# Thermometers.net
KiCad netlist of a schematic drawn in Altium Designer
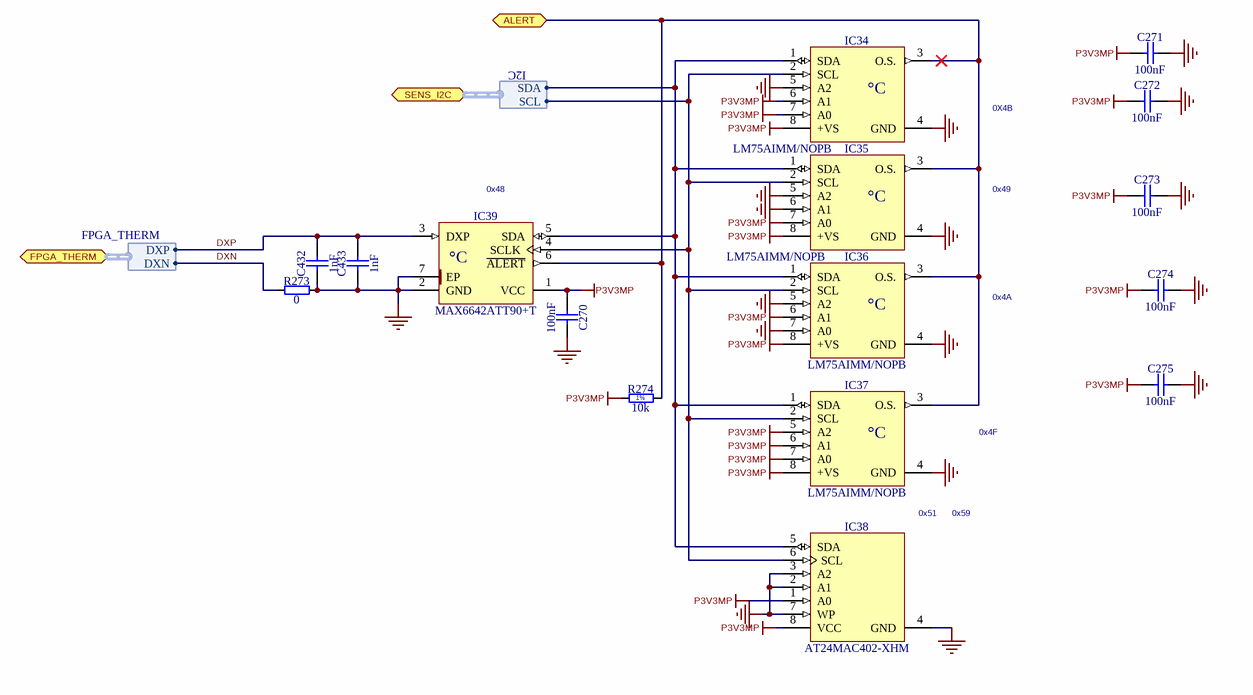
[diagram p0: Thermometers.SchDoc]

(export (version "E")
  (design (tool "Eeschema 10.0.6"))
  (components
    (comp (ref "C270")
      (value "100nF")
      (footprint "CAPC0603X33N")
      (description "Non-polarised capacitor")
      (fields
        (field (name "MANUFACTURER PART NUMBER") "CC0201_100NF_6.3V_10%_X5R")
        (field (name "MANUFACTURER") "GENERIC")
        (field (name "AUTHOR") "CERN DEM JLC")
      )
      (libsource (lib "Capacitors") (part "Capacitor - non polarized"))
    )
    (comp (ref "C271")
      (value "100nF")
      (footprint "CAPC0603X33N")
      (description "Non-polarised capacitor")
      (fields
        (field (name "MANUFACTURER PART NUMBER") "CC0201_100NF_6.3V_10%_X5R")
        (field (name "MANUFACTURER") "GENERIC")
        (field (name "AUTHOR") "CERN DEM JLC")
      )
      (libsource (lib "Capacitors") (part "Capacitor - non polarized"))
    )
    (comp (ref "C272")
      (value "100nF")
      (footprint "CAPC0603X33N")
      (description "Non-polarised capacitor")
      (fields
        (field (name "MANUFACTURER PART NUMBER") "CC0201_100NF_6.3V_10%_X5R")
        (field (name "MANUFACTURER") "GENERIC")
        (field (name "AUTHOR") "CERN DEM JLC")
      )
      (libsource (lib "Capacitors") (part "Capacitor - non polarized"))
    )
    (comp (ref "C273")
      (value "100nF")
      (footprint "CAPC0603X33N")
      (description "Non-polarised capacitor")
      (fields
        (field (name "MANUFACTURER PART NUMBER") "CC0201_100NF_6.3V_10%_X5R")
        (field (name "MANUFACTURER") "GENERIC")
        (field (name "AUTHOR") "CERN DEM JLC")
      )
      (libsource (lib "Capacitors") (part "Capacitor - non polarized"))
    )
    (comp (ref "C274")
      (value "100nF")
      (footprint "CAPC0603X33N")
      (description "Non-polarised capacitor")
      (fields
        (field (name "MANUFACTURER PART NUMBER") "CC0201_100NF_6.3V_10%_X5R")
        (field (name "MANUFACTURER") "GENERIC")
        (field (name "AUTHOR") "CERN DEM JLC")
      )
      (libsource (lib "Capacitors") (part "Capacitor - non polarized"))
    )
    (comp (ref "C275")
      (value "100nF")
      (footprint "CAPC0603X33N")
      (description "Non-polarised capacitor")
      (fields
        (field (name "MANUFACTURER PART NUMBER") "CC0201_100NF_6.3V_10%_X5R")
        (field (name "MANUFACTURER") "GENERIC")
        (field (name "AUTHOR") "CERN DEM JLC")
      )
      (libsource (lib "Capacitors") (part "Capacitor - non polarized"))
    )
    (comp (ref "C432")
      (value "1nF")
      (footprint "CAPC1005X55N")
      (description "Non-polarised capacitor")
      (fields
        (field (name "MANUFACTURER PART NUMBER") "CC0402_1NF_50V_10%_X7R")
        (field (name "MANUFACTURER") "GENERIC")
        (field (name "AUTHOR") "CERN DEM JLC")
      )
      (libsource (lib "Capacitors") (part "Capacitor - non polarized"))
    )
    (comp (ref "C433")
      (value "1nF")
      (footprint "CAPC1005X55N")
      (description "Non-polarised capacitor")
      (fields
        (field (name "MANUFACTURER PART NUMBER") "CC0402_1NF_50V_10%_X7R")
        (field (name "MANUFACTURER") "GENERIC")
        (field (name "AUTHOR") "CERN DEM JLC")
      )
      (libsource (lib "Capacitors") (part "Capacitor - non polarized"))
    )
    (comp (ref "IC34")
      (value "LM75AIMM/NOPB")
      (footprint "SOP65P490X109-8N")
      (description "Digital Temperature Sensor and Thermal Watchdog with Two-Wire Interface")
      (fields (field (name "MANUFACTURER") "TEXAS INSTRUMENTS") (field (name "AUTHOR") "CERN DEM JLC"))
      (libsource (lib "ICs And Semiconductors") (part "LM75"))
    )
    (comp (ref "IC35")
      (value "LM75AIMM/NOPB")
      (footprint "SOP65P490X109-8N")
      (description "Digital Temperature Sensor and Thermal Watchdog with Two-Wire Interface")
      (fields (field (name "MANUFACTURER") "TEXAS INSTRUMENTS") (field (name "AUTHOR") "CERN DEM JLC"))
      (libsource (lib "ICs And Semiconductors") (part "LM75"))
    )
    (comp (ref "IC36")
      (value "LM75AIMM/NOPB")
      (footprint "SOP65P490X109-8N")
      (description "Digital Temperature Sensor and Thermal Watchdog with Two-Wire Interface")
      (fields (field (name "MANUFACTURER") "TEXAS INSTRUMENTS") (field (name "AUTHOR") "CERN DEM JLC"))
      (libsource (lib "ICs And Semiconductors") (part "LM75"))
    )
    (comp (ref "IC37")
      (value "LM75AIMM/NOPB")
      (footprint "SOP65P490X109-8N")
      (description "Digital Temperature Sensor and Thermal Watchdog with Two-Wire Interface")
      (fields (field (name "MANUFACTURER") "TEXAS INSTRUMENTS") (field (name "AUTHOR") "CERN DEM JLC"))
      (libsource (lib "ICs And Semiconductors") (part "LM75"))
    )
    (comp (ref "IC38")
      (value "AT24MAC402-XHM")
      (footprint "SOP65P640X120-8N")
      (description "1.7V to 5.5V, I2C-Compatible (2-wire) 2-Kbit (256 x 8) Serial EEPROM")
      (fields (field (name "MANUFACTURER") "ATMEL") (field (name "AUTHOR") "CERN DEM MR"))
      (libsource (lib "ICs And Semiconductors") (part "AT24MAC402-XHM"))
    )
    (comp (ref "IC39")
      (value "MAX6642ATT90+T")
      (footprint "SON95P300X300X80-7N-R160X240")
      (description "±1°C, SMBus-Compatible Remote/Local Temperature Sensor with Overtemperature Alarm")
      (fields (field (name "MANUFACTURER") "MAXIM") (field (name "AUTHOR") "CERN DEM JLC"))
      (libsource (lib "ICs And Semiconductors") (part "MAX6642ATT"))
    )
    (comp (ref "R273")
      (value "0")
      (footprint "RESC1005X40N")
      (description "Resistor")
      (fields
        (field (name "MANUFACTURER PART NUMBER") "R0402_0R_JUMPER")
        (field (name "MANUFACTURER") "GENERIC")
        (field (name "AUTHOR") "CERN DEM JLC")
      )
      (libsource (lib "Resistors") (part "Resistor"))
    )
    (comp (ref "R274")
      (value "10k")
      (footprint "RESC1005X40N")
      (description "Resistor - 1%")
      (fields
        (field (name "MANUFACTURER PART NUMBER") "R0402_10K_1%_0.0625W_100PPM")
        (field (name "MANUFACTURER") "GENERIC")
        (field (name "AUTHOR") "CERN DEM JLC")
      )
      (libsource (lib "Resistors") (part "Resistor - 1%"))
    )
  )
  (nets
    (net (code "3") (name "/ALERT") (class "Default")
      (node (ref "IC34") (pin "3") (pinfunction "O.S._3") (pintype "output"))
      (node (ref "IC35") (pin "3") (pinfunction "O.S._3") (pintype "output"))
      (node (ref "IC36") (pin "3") (pinfunction "O.S._3") (pintype "output"))
      (node (ref "IC37") (pin "3") (pinfunction "O.S._3") (pintype "output"))
      (node (ref "IC39") (pin "6") (pinfunction "~{ALERT}_6") (pintype "output"))
      (node (ref "R274") (pin "2") (pinfunction "2_2") (pintype "passive"))
    )
    (net (code "4") (name "/DXN") (class "Default")
      (node (ref "R273") (pin "1") (pinfunction "1_1") (pintype "passive"))
    )
    (net (code "5") (name "/DXP") (class "Default")
      (node (ref "C432") (pin "2") (pinfunction "2_2") (pintype "passive"))
      (node (ref "C433") (pin "2") (pinfunction "2_2") (pintype "passive"))
      (node (ref "IC39") (pin "3") (pinfunction "DXP_3") (pintype "input"))
    )
    (net (code "8") (name "GND") (class "Default")
      (node (ref "C270") (pin "1") (pinfunction "1_1") (pintype "passive"))
      (node (ref "C271") (pin "2") (pinfunction "2_2") (pintype "passive"))
      (node (ref "C272") (pin "2") (pinfunction "2_2") (pintype "passive"))
      (node (ref "C273") (pin "2") (pinfunction "2_2") (pintype "passive"))
      (node (ref "C274") (pin "2") (pinfunction "2_2") (pintype "passive"))
      (node (ref "C275") (pin "2") (pinfunction "2_2") (pintype "passive"))
      (node (ref "C432") (pin "1") (pinfunction "1_1") (pintype "passive"))
      (node (ref "C433") (pin "1") (pinfunction "1_1") (pintype "passive"))
      (node (ref "IC34") (pin "4") (pinfunction "GND_4") (pintype "power_in"))
      (node (ref "IC34") (pin "5") (pinfunction "A2_5") (pintype "input"))
      (node (ref "IC35") (pin "4") (pinfunction "GND_4") (pintype "power_in"))
      (node (ref "IC35") (pin "5") (pinfunction "A2_5") (pintype "input"))
      (node (ref "IC35") (pin "6") (pinfunction "A1_6") (pintype "input"))
      (node (ref "IC36") (pin "4") (pinfunction "GND_4") (pintype "power_in"))
      (node (ref "IC36") (pin "5") (pinfunction "A2_5") (pintype "input"))
      (node (ref "IC36") (pin "7") (pinfunction "A0_7") (pintype "input"))
      (node (ref "IC37") (pin "4") (pinfunction "GND_4") (pintype "power_in"))
      (node (ref "IC38") (pin "2") (pinfunction "A1_2") (pintype "input"))
      (node (ref "IC38") (pin "3") (pinfunction "A2_3") (pintype "input"))
      (node (ref "IC38") (pin "4") (pinfunction "GND_4") (pintype "power_in"))
      (node (ref "IC38") (pin "7") (pinfunction "WP_7") (pintype "input"))
      (node (ref "IC39") (pin "2") (pinfunction "GND_2") (pintype "power_in"))
      (node (ref "IC39") (pin "7") (pinfunction "EP_7") (pintype "power_in"))
      (node (ref "R273") (pin "2") (pinfunction "2_2") (pintype "passive"))
    )
    (net (code "9") (name "Net-(IC34-SCL)") (class "Default")
      (node (ref "IC34") (pin "2") (pinfunction "SCL_2") (pintype "input"))
      (node (ref "IC35") (pin "2") (pinfunction "SCL_2") (pintype "input"))
      (node (ref "IC36") (pin "2") (pinfunction "SCL_2") (pintype "input"))
      (node (ref "IC37") (pin "2") (pinfunction "SCL_2") (pintype "input"))
      (node (ref "IC38") (pin "6") (pinfunction "SCL_6") (pintype "input"))
      (node (ref "IC39") (pin "4") (pinfunction "SCLK_4") (pintype "input"))
    )
    (net (code "10") (name "Net-(IC34-SDA)") (class "Default")
      (node (ref "IC34") (pin "1") (pinfunction "SDA_1") (pintype "bidirectional"))
      (node (ref "IC35") (pin "1") (pinfunction "SDA_1") (pintype "bidirectional"))
      (node (ref "IC36") (pin "1") (pinfunction "SDA_1") (pintype "bidirectional"))
      (node (ref "IC37") (pin "1") (pinfunction "SDA_1") (pintype "bidirectional"))
      (node (ref "IC38") (pin "5") (pinfunction "SDA_5") (pintype "bidirectional"))
      (node (ref "IC39") (pin "5") (pinfunction "SDA_5") (pintype "bidirectional"))
    )
    (net (code "11") (name "P3V3MP") (class "Default")
      (node (ref "C270") (pin "2") (pinfunction "2_2") (pintype "passive"))
      (node (ref "C271") (pin "1") (pinfunction "1_1") (pintype "passive"))
      (node (ref "C272") (pin "1") (pinfunction "1_1") (pintype "passive"))
      (node (ref "C273") (pin "1") (pinfunction "1_1") (pintype "passive"))
      (node (ref "C274") (pin "1") (pinfunction "1_1") (pintype "passive"))
      (node (ref "C275") (pin "1") (pinfunction "1_1") (pintype "passive"))
      (node (ref "IC34") (pin "6") (pinfunction "A1_6") (pintype "input"))
      (node (ref "IC34") (pin "7") (pinfunction "A0_7") (pintype "input"))
      (node (ref "IC34") (pin "8") (pinfunction "+VS_8") (pintype "power_in"))
      (node (ref "IC35") (pin "7") (pinfunction "A0_7") (pintype "input"))
      (node (ref "IC35") (pin "8") (pinfunction "+VS_8") (pintype "power_in"))
      (node (ref "IC36") (pin "6") (pinfunction "A1_6") (pintype "input"))
      (node (ref "IC36") (pin "8") (pinfunction "+VS_8") (pintype "power_in"))
      (node (ref "IC37") (pin "5") (pinfunction "A2_5") (pintype "input"))
      (node (ref "IC37") (pin "6") (pinfunction "A1_6") (pintype "input"))
      (node (ref "IC37") (pin "7") (pinfunction "A0_7") (pintype "input"))
      (node (ref "IC37") (pin "8") (pinfunction "+VS_8") (pintype "power_in"))
      (node (ref "IC38") (pin "1") (pinfunction "A0_1") (pintype "input"))
      (node (ref "IC38") (pin "8") (pinfunction "VCC_8") (pintype "power_in"))
      (node (ref "IC39") (pin "1") (pinfunction "VCC_1") (pintype "power_in"))
      (node (ref "R274") (pin "1") (pinfunction "1_1") (pintype "passive"))
    )
  )
)
